# SBG.net
KiCad netlist of a schematic drawn in Altium Designer
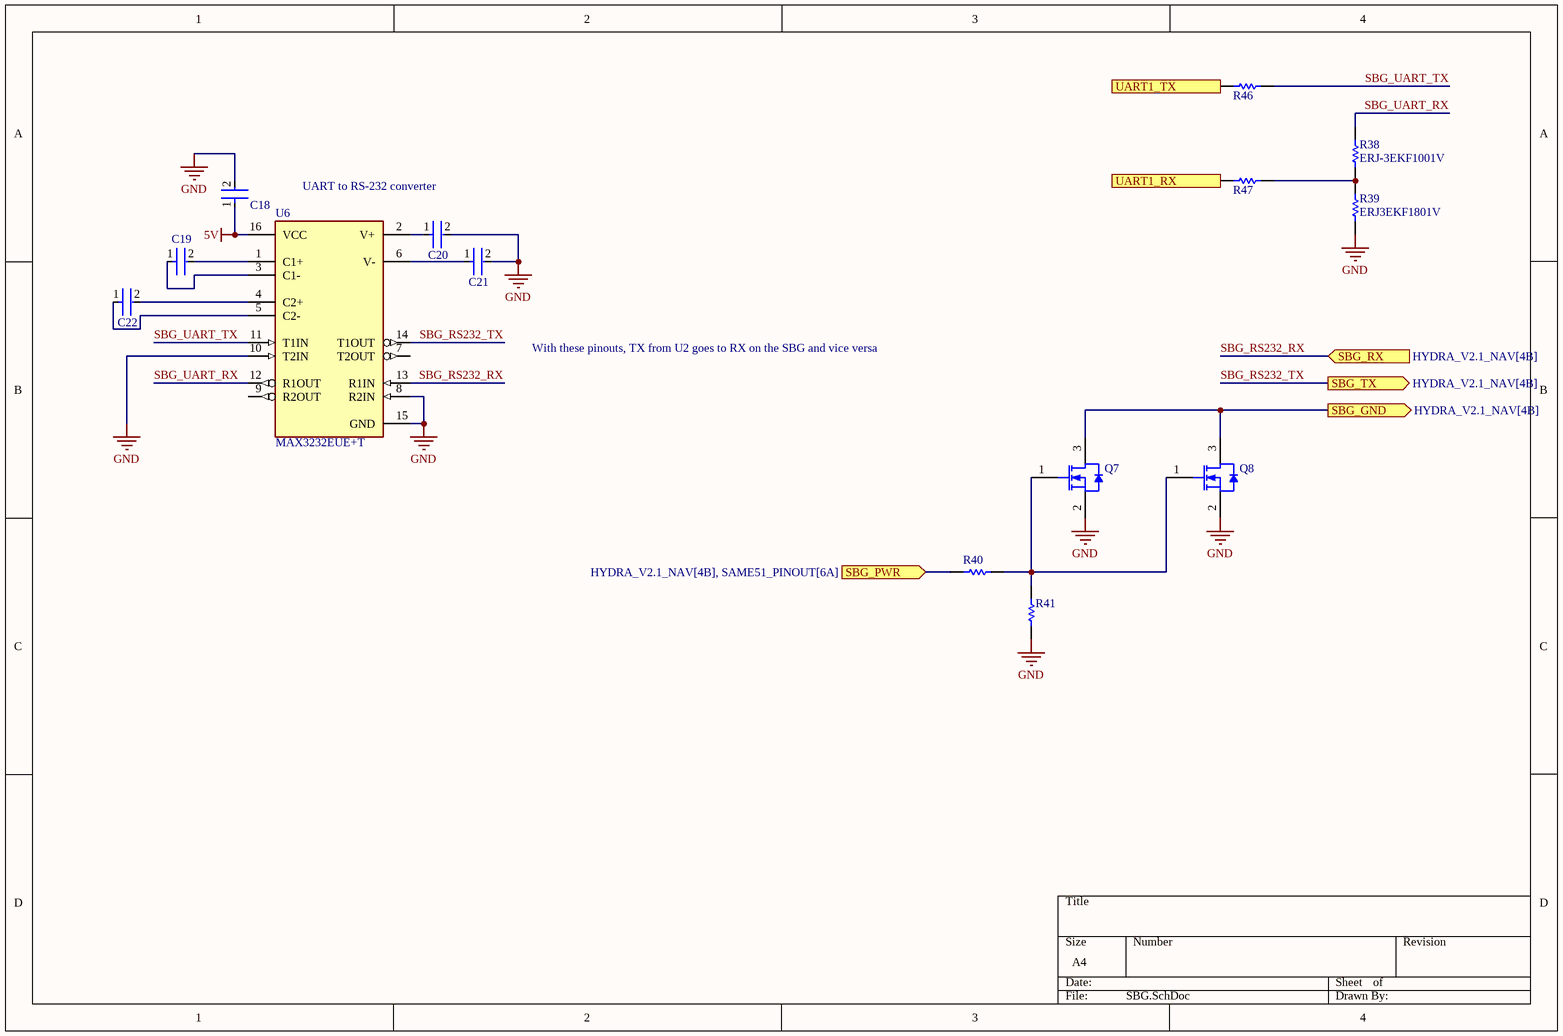
[diagram p0: SBG.SchDoc]

(export (version "E")
  (design (tool "Eeschema 10.0.6"))
  (components
    (comp (ref "C18")
      (value "C0402C104K8PACTU")
      (footprint "FP-C0402-BB-MFG")
      (description "CAP CER 0.1UF 10V X5R 0402")
      (fields (field (name "MANUFACTURER") "Kemet") (field (name "TOLERANCE") "0.1"))
      (libsource (lib "Altium Content Vault") (part "b4654b650e69147ec39a6b967a45e02"))
    )
    (comp (ref "C19")
      (value "C1005X5R1A475K050BC")
      (footprint "FP-C1005-050-0_15-MFG")
      (description "CAP CER 4.7UF 10V X5R 0402")
      (fields (field (name "TOLERANCE") "10%"))
      (libsource (lib "Altium Content Vault") (part "b4654b650e69147ec39a6b967a45e02"))
    )
    (comp (ref "C20")
      (value "C1005X5R1V334K050BC")
      (footprint "FP-C1005-050-0_05-IPC_B")
      (description "Multilayer Ceramic Capacitors 330nF ±10% 35V X5R SMD 0402")
      (fields (field (name "TOLERANCE") "10%"))
      (libsource (lib "Altium Content Vault") (part "b4654b650e69147ec39a6b967a45e02"))
    )
    (comp (ref "C21")
      (value "C1005X5R1V334K050BC")
      (footprint "FP-C1005-050-0_05-IPC_B")
      (description "Multilayer Ceramic Capacitors 330nF ±10% 35V X5R SMD 0402")
      (fields (field (name "TOLERANCE") "10%"))
      (libsource (lib "Altium Content Vault") (part "b4654b650e69147ec39a6b967a45e02"))
    )
    (comp (ref "C22")
      (value "C1005X5R1V334K050BC")
      (footprint "FP-C1005-050-0_05-IPC_B")
      (description "Multilayer Ceramic Capacitors 330nF ±10% 35V X5R SMD 0402")
      (fields (field (name "TOLERANCE") "10%"))
      (libsource (lib "Altium Content Vault") (part "b4654b650e69147ec39a6b967a45e02"))
    )
    (comp (ref "Q7")
      (value "BSS138W-7-F")
      (footprint "DIOD-SOT323-3_V")
      (fields (field (name "MANUFACTURER") "DiodesIncorporated"))
      (libsource (lib "Altium Content Vault") (part "NEMOS-GSD-3"))
    )
    (comp (ref "Q8")
      (value "BSS138W-7-F")
      (footprint "DIOD-SOT323-3_V")
      (fields (field (name "MANUFACTURER") "DiodesIncorporated"))
      (libsource (lib "Altium Content Vault") (part "NEMOS-GSD-3"))
    )
    (comp (ref "R38")
      (value "ERJ-3EKF1001V")
      (footprint "RESC1608X55X30LL15T15")
      (fields (field (name "MANUFACTURER") "Panasonic"))
      (libsource (lib "Altium Content Vault") (part "RES"))
    )
    (comp (ref "R39")
      (value "ERJ3EKF1801V")
      (footprint "RESC1608X55X30LL15T15")
      (fields (field (name "MANUFACTURER") "Panasonic"))
      (libsource (lib "Altium Content Vault") (part "RES"))
    )
    (comp (ref "R40")
      (value "ERJ-3EKF1001V")
      (footprint "RESC1608X55X30LL15T15")
      (fields (field (name "MANUFACTURER") "Panasonic"))
      (libsource (lib "Altium Content Vault") (part "RES"))
    )
    (comp (ref "R41")
      (value "ERJ3EKF1002V")
      (footprint "RESC1609X55X30LL15T15")
      (description "Chip Resistor, 10 KOhm, +/- 1%, 0.1 W, -55 to 155 degC, 0603 (1608 Metric), RoHS, Tape and Reel")
      (fields (field (name "TOLERANCE") "1%") (field (name "MANUFACTURER") "Panasonic"))
      (libsource (lib "Altium Content Vault") (part "RES-2"))
    )
    (comp (ref "R46")
      (value "0402 JUMPER 0 OHM")
      (footprint "RESC1005X40X25NL05T05")
      (description "READ THE NAME")
      (libsource (lib "uORocketry Hardware") (part "RES"))
    )
    (comp (ref "R47")
      (value "0402 JUMPER 0 OHM")
      (footprint "RESC1005X40X25NL05T05")
      (description "READ THE NAME")
      (libsource (lib "uORocketry Hardware") (part "RES"))
    )
    (comp (ref "U6")
      (value "MAX3232EUE+T")
      (footprint "FP-U16-1-MFG")
      (description "IC TXRX RS-232 LP 16-TSSOP")
      (fields
        (field (name "OCTOPART") "https://octopart.com/max3232eue%2Bt-maxim+integrated-39814427")
        (field (name "MANUFACTURER") "Maxim Integrated")
      )
      (libsource (lib "Altium Content Vault") (part "753fb76a544055c619a09297c280b9d"))
    )
  )
  (nets
    (net (code "1") (name "/SBG_GND") (class "Default")
      (node (ref "Q7") (pin "3") (pinfunction "D_3") (pintype "passive"))
      (node (ref "Q8") (pin "3") (pinfunction "D_3") (pintype "passive"))
    )
    (net (code "2") (name "/SBG_PWR") (class "Default")
      (node (ref "R40") (pin "1") (pinfunction "1_1") (pintype "passive"))
    )
    (net (code "3") (name "/SBG_RS232_RX") (class "Default")
      (node (ref "U6") (pin "13") (pinfunction "R1IN_13") (pintype "input"))
    )
    (net (code "4") (name "/SBG_RS232_TX") (class "Default")
      (node (ref "U6") (pin "14") (pinfunction "T1OUT_14") (pintype "output"))
    )
    (net (code "5") (name "/SBG_UART_RX") (class "Default")
      (node (ref "R38") (pin "2") (pinfunction "2_2") (pintype "passive"))
      (node (ref "U6") (pin "12") (pinfunction "R1OUT_12") (pintype "output"))
    )
    (net (code "6") (name "/SBG_UART_TX") (class "Default")
      (node (ref "R46") (pin "2") (pinfunction "2_2") (pintype "passive"))
      (node (ref "U6") (pin "11") (pinfunction "T1IN_11") (pintype "input"))
    )
    (net (code "7") (name "/UART1_RX") (class "Default")
      (node (ref "R47") (pin "1") (pinfunction "1_1") (pintype "passive"))
    )
    (net (code "8") (name "/UART1_TX") (class "Default")
      (node (ref "R46") (pin "1") (pinfunction "1_1") (pintype "passive"))
    )
    (net (code "9") (name "5V") (class "Default")
      (node (ref "C18") (pin "1") (pinfunction "1_1") (pintype "passive"))
      (node (ref "U6") (pin "16") (pinfunction "VCC_16") (pintype "power_in"))
    )
    (net (code "10") (name "GND") (class "Default")
      (node (ref "C18") (pin "2") (pinfunction "2_2") (pintype "passive"))
      (node (ref "C20") (pin "2") (pinfunction "2_2") (pintype "passive"))
      (node (ref "C21") (pin "2") (pinfunction "2_2") (pintype "passive"))
      (node (ref "Q7") (pin "2") (pinfunction "S_2") (pintype "passive"))
      (node (ref "Q8") (pin "2") (pinfunction "S_2") (pintype "passive"))
      (node (ref "R39") (pin "1") (pinfunction "1_1") (pintype "passive"))
      (node (ref "R41") (pin "1") (pinfunction "1_1") (pintype "passive"))
      (node (ref "U6") (pin "10") (pinfunction "T2IN_10") (pintype "input"))
      (node (ref "U6") (pin "15") (pinfunction "GND_15") (pintype "power_in"))
      (node (ref "U6") (pin "8") (pinfunction "R2IN_8") (pintype "input"))
    )
    (net (code "11") (name "Net-(Q7-G)") (class "Default")
      (node (ref "Q7") (pin "1") (pinfunction "G_1") (pintype "passive"))
      (node (ref "Q8") (pin "1") (pinfunction "G_1") (pintype "passive"))
      (node (ref "R40") (pin "2") (pinfunction "2_2") (pintype "passive"))
      (node (ref "R41") (pin "2") (pinfunction "2_2") (pintype "passive"))
    )
    (net (code "12") (name "Net-(R38-Pad1)") (class "Default")
      (node (ref "R38") (pin "1") (pinfunction "1_1") (pintype "passive"))
      (node (ref "R39") (pin "2") (pinfunction "2_2") (pintype "passive"))
      (node (ref "R47") (pin "2") (pinfunction "2_2") (pintype "passive"))
    )
    (net (code "13") (name "Net-(U6-C1+)") (class "Default")
      (node (ref "C19") (pin "2") (pinfunction "2_2") (pintype "passive"))
      (node (ref "U6") (pin "1") (pinfunction "C1+_1") (pintype "passive"))
    )
    (net (code "14") (name "Net-(U6-C1-)") (class "Default")
      (node (ref "C19") (pin "1") (pinfunction "1_1") (pintype "passive"))
      (node (ref "U6") (pin "3") (pinfunction "C1-_3") (pintype "passive"))
    )
    (net (code "15") (name "Net-(U6-C2+)") (class "Default")
      (node (ref "C22") (pin "2") (pinfunction "2_2") (pintype "passive"))
      (node (ref "U6") (pin "4") (pinfunction "C2+_4") (pintype "passive"))
    )
    (net (code "16") (name "Net-(U6-C2-)") (class "Default")
      (node (ref "C22") (pin "1") (pinfunction "1_1") (pintype "passive"))
      (node (ref "U6") (pin "5") (pinfunction "C2-_5") (pintype "passive"))
    )
    (net (code "17") (name "Net-(U6-V+)") (class "Default")
      (node (ref "C20") (pin "1") (pinfunction "1_1") (pintype "passive"))
      (node (ref "U6") (pin "2") (pinfunction "V+_2") (pintype "power_in"))
    )
    (net (code "18") (name "Net-(U6-V-)") (class "Default")
      (node (ref "C21") (pin "1") (pinfunction "1_1") (pintype "passive"))
      (node (ref "U6") (pin "6") (pinfunction "V-_6") (pintype "power_in"))
    )
    (net (code "19") (name "unconnected-(U6-R2OUT-Pad9)") (class "Default")
      (node (ref "U6") (pin "9") (pinfunction "R2OUT_9") (pintype "output"))
    )
    (net (code "20") (name "unconnected-(U6-T2OUT-Pad7)") (class "Default")
      (node (ref "U6") (pin "7") (pinfunction "T2OUT_7") (pintype "output"))
    )
  )
)
